# 06-MAC.net
KiCad netlist of a schematic drawn in Altium Designer
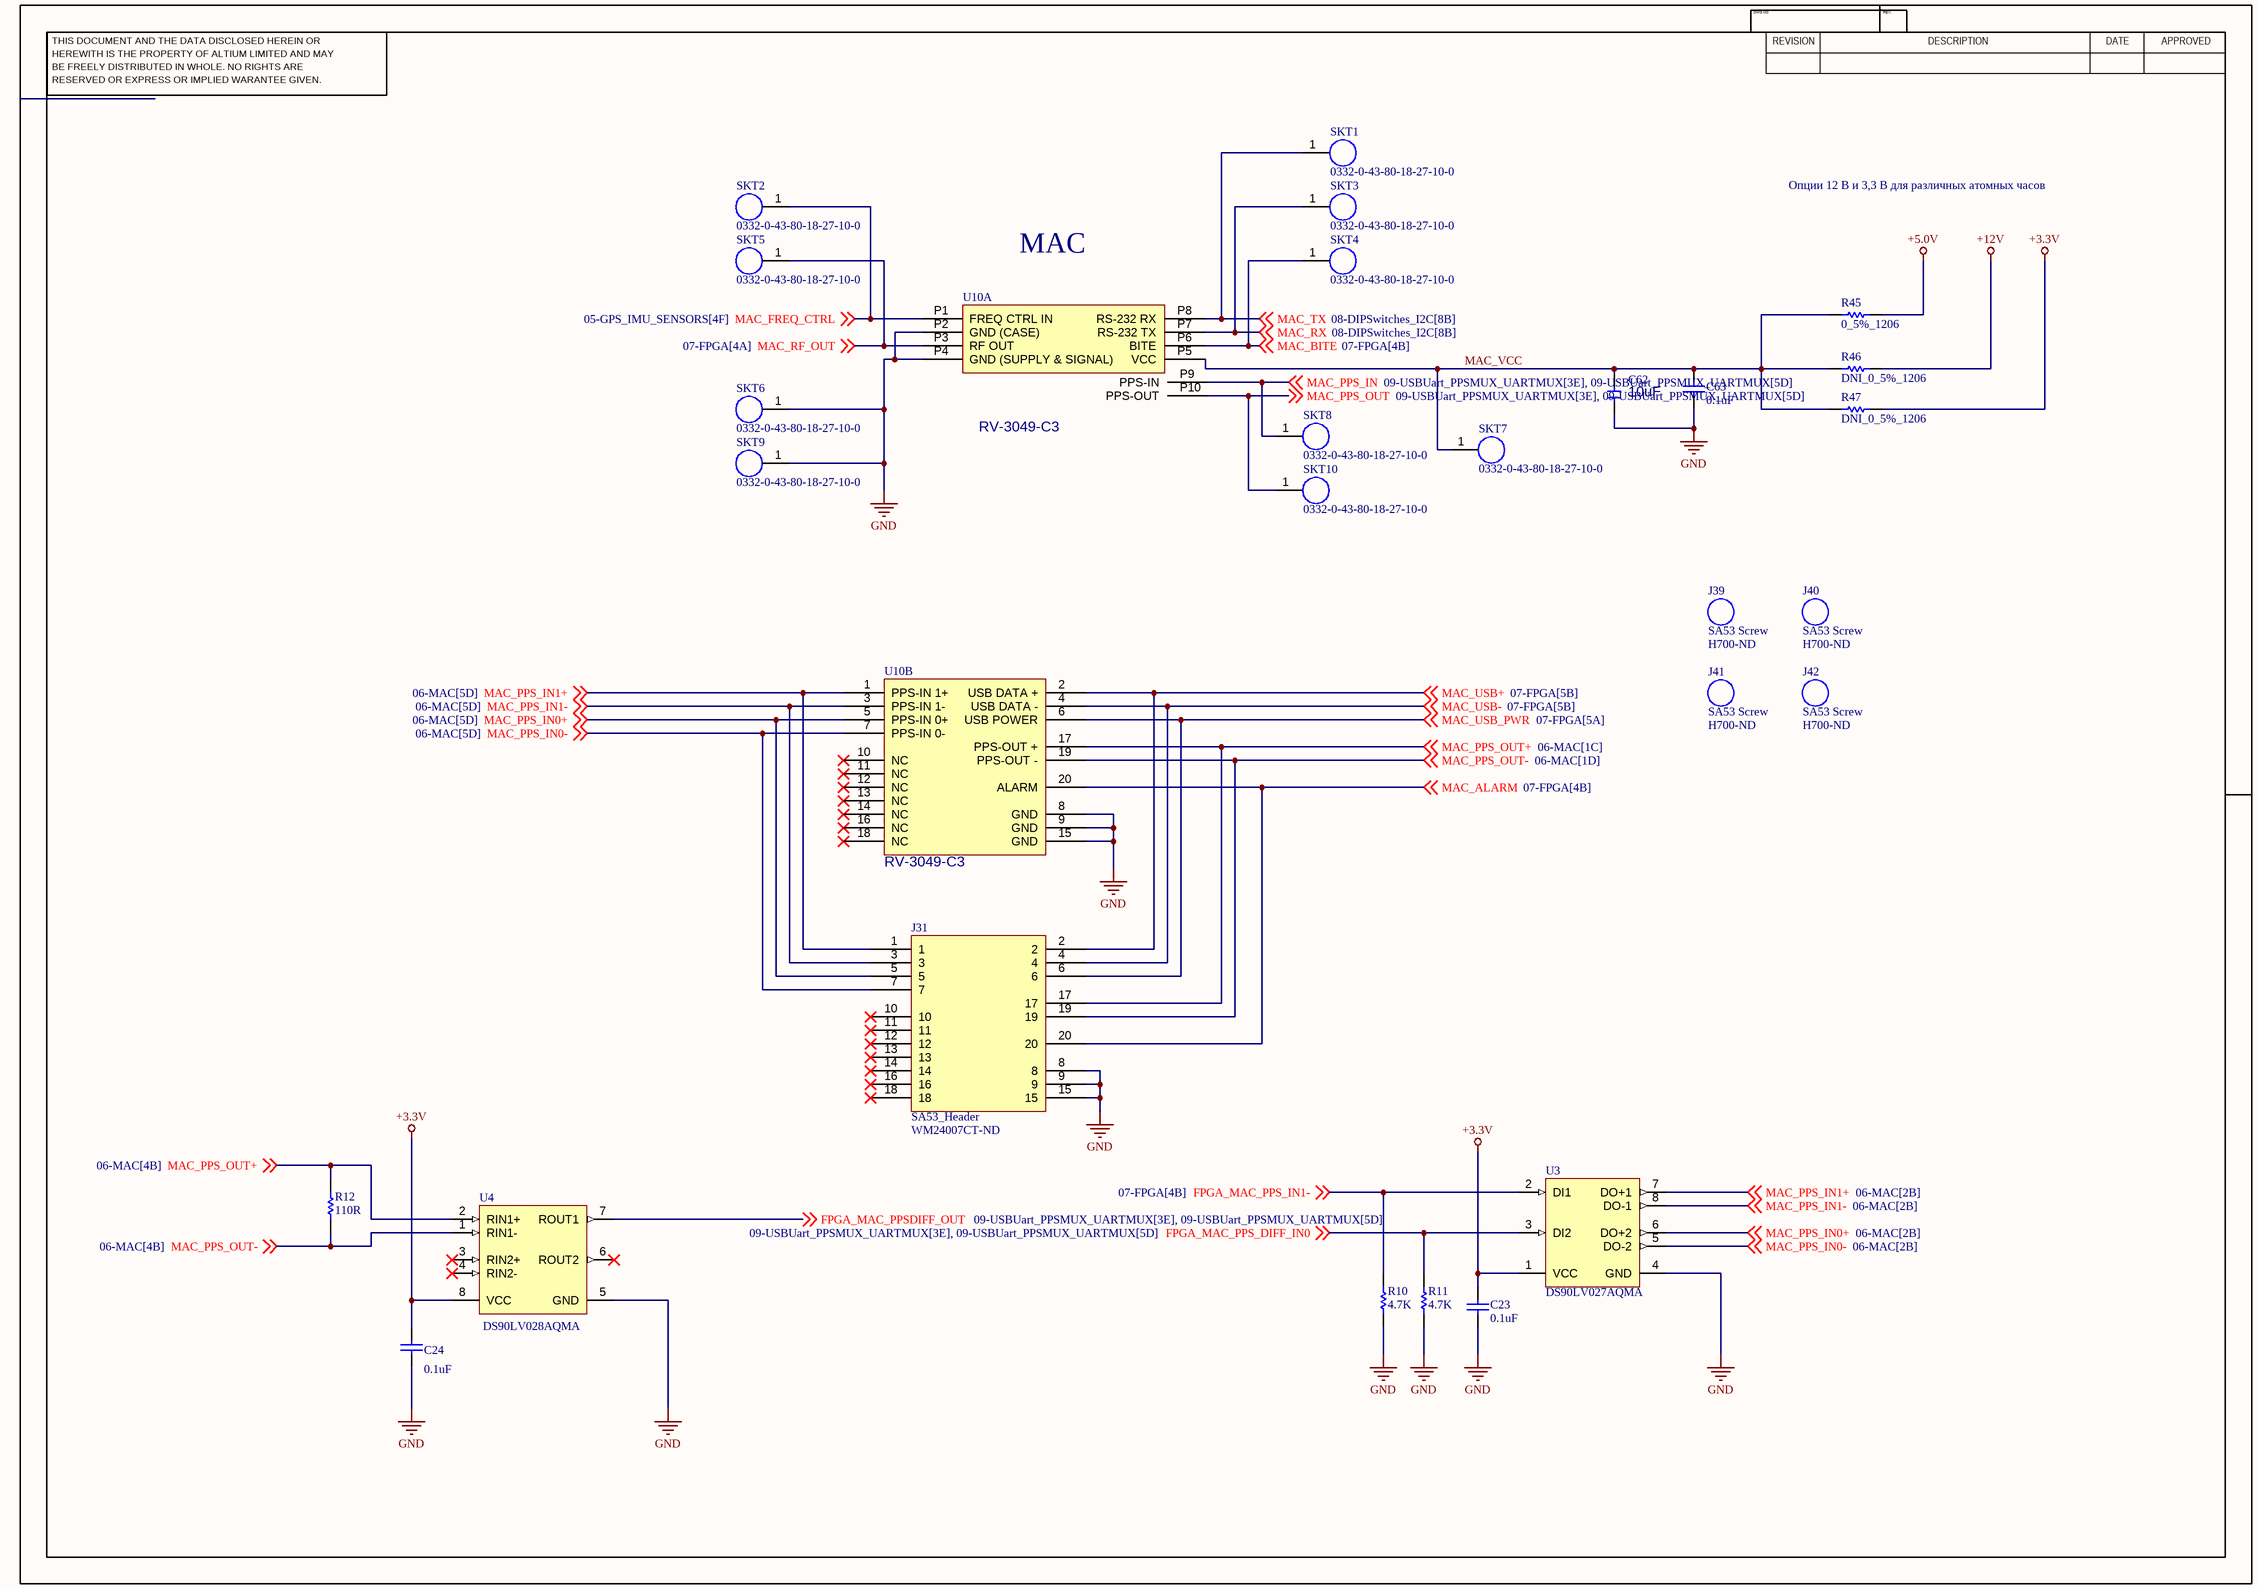
[diagram p0: 06-MAC.SchDoc]

(export (version "E")
  (design (tool "Eeschema 10.0.6"))
  (components
    (comp (ref "C23")
      (value "0.1uF")
      (footprint "CAPC1608X87X45ML20T05")
      (description "C0603X104K5RACAUTO")
      (fields (field (name "MANUFACTURER") "Kemet"))
      (libsource (lib "Altium Content Vault") (part "CAP"))
    )
    (comp (ref "C24")
      (value "0.1uF")
      (footprint "CAPC1608X87X45ML20T05")
      (description "C0603X104K5RACAUTO")
      (fields (field (name "MANUFACTURER") "Kemet"))
      (libsource (lib "Altium Content Vault") (part "CAP"))
    )
    (comp (ref "C62")
      (value "10uF")
      (footprint "CAPC2012X14N")
      (description "CAP, CER, 10.UF, 25V, 10%, X5R, 0805")
      (fields
        (field (name "MFG PART NUM") "TMK212BBJ106KG-T")
        (field (name "VALENTIUM PART NUM") "<VALENTIUM>")
      )
      (libsource (lib "Capacitors") (part "CAP_0805_10UF_25V"))
    )
    (comp (ref "C63")
      (value "0.1uF")
      (footprint "CAPC1608X87X45ML20T05")
      (description "C0603X104K5RACAUTO")
      (fields (field (name "MANUFACTURER") "Kemet"))
      (libsource (lib "Altium Content Vault") (part "CAP"))
    )
    (comp (ref "J31")
      (value "SA53_Header")
      (footprint "SA53_Header")
      (fields (field (name "SUPPLIER PART NUMBER 1") "WM24007CT-ND"))
      (libsource (lib "FPGA_CONN") (part "SA53_Header"))
    )
    (comp (ref "J39")
      (value "SA53 Screw")
      (fields (field (name "SUPPLIER PART NUMBER 1") "H700-ND"))
      (libsource (lib "FPGA_CONN") (part "SA53 Screw"))
    )
    (comp (ref "J40")
      (value "SA53 Screw")
      (fields (field (name "SUPPLIER PART NUMBER 1") "H700-ND"))
      (libsource (lib "FPGA_CONN") (part "SA53 Screw"))
    )
    (comp (ref "J41")
      (value "SA53 Screw")
      (fields (field (name "SUPPLIER PART NUMBER 1") "H700-ND"))
      (libsource (lib "FPGA_CONN") (part "SA53 Screw"))
    )
    (comp (ref "J42")
      (value "SA53 Screw")
      (fields (field (name "SUPPLIER PART NUMBER 1") "H700-ND"))
      (libsource (lib "FPGA_CONN") (part "SA53 Screw"))
    )
    (comp (ref "R10")
      (value "4.7K")
      (footprint "RESC1608X55X25LL10T15")
      (fields (field (name "MANUFACTURER") "Yageo") (field (name "TOLERANCE") "1%"))
      (libsource (lib "Altium Content Vault") (part "RES-2"))
    )
    (comp (ref "R11")
      (value "4.7K")
      (footprint "RESC1608X55X25LL10T15")
      (fields (field (name "MANUFACTURER") "Yageo") (field (name "TOLERANCE") "1%"))
      (libsource (lib "Altium Content Vault") (part "RES-2"))
    )
    (comp (ref "R12")
      (value "110R")
      (footprint "RESC1609X50X30NL10T20")
      (fields (field (name "PART NUMBER") "CRCW0603110RFKEA") (field (name "MANUFACTURER") "Vishay Dale"))
      (libsource (lib "Altium Content Vault") (part "RES"))
    )
    (comp (ref "R45")
      (value "0_5%_1206")
      (footprint "RESC3116X65X50ML20T20")
      (fields (field (name "PART NUMBER") "CRCW12060000Z0EAHP") (field (name "MANUFACTURER") "Vishay Dale"))
      (libsource (lib "Altium Content Vault") (part "RES"))
    )
    (comp (ref "R46")
      (value "DNI_0_5%_1206")
      (footprint "RESC3116X65X50ML20T20")
      (fields (field (name "PART NUMBER") "CRCW12060000Z0EAHP") (field (name "MANUFACTURER") "Vishay Dale"))
      (libsource (lib "Altium Content Vault") (part "RES"))
    )
    (comp (ref "R47")
      (value "DNI_0_5%_1206")
      (footprint "RESC3116X65X50ML20T20")
      (fields (field (name "PART NUMBER") "CRCW12060000Z0EAHP") (field (name "MANUFACTURER") "Vishay Dale"))
      (libsource (lib "Altium Content Vault") (part "RES"))
    )
    (comp (ref "SKT1")
      (value "0332-0-43-80-18-27-10-0")
      (footprint "SolderSocket")
      (description "Solder socket for pin headers")
      (libsource (lib "FPGA_CONN") (part "0332-0-43-80-18-27-10-0"))
    )
    (comp (ref "SKT2")
      (value "0332-0-43-80-18-27-10-0")
      (footprint "SolderSocket")
      (description "Solder socket for pin headers")
      (libsource (lib "FPGA_CONN") (part "0332-0-43-80-18-27-10-0"))
    )
    (comp (ref "SKT3")
      (value "0332-0-43-80-18-27-10-0")
      (footprint "SolderSocket")
      (description "Solder socket for pin headers")
      (libsource (lib "FPGA_CONN") (part "0332-0-43-80-18-27-10-0"))
    )
    (comp (ref "SKT4")
      (value "0332-0-43-80-18-27-10-0")
      (footprint "SolderSocket")
      (description "Solder socket for pin headers")
      (libsource (lib "FPGA_CONN") (part "0332-0-43-80-18-27-10-0"))
    )
    (comp (ref "SKT5")
      (value "0332-0-43-80-18-27-10-0")
      (footprint "SolderSocket")
      (description "Solder socket for pin headers")
      (libsource (lib "FPGA_CONN") (part "0332-0-43-80-18-27-10-0"))
    )
    (comp (ref "SKT6")
      (value "0332-0-43-80-18-27-10-0")
      (footprint "SolderSocket")
      (description "Solder socket for pin headers")
      (libsource (lib "FPGA_CONN") (part "0332-0-43-80-18-27-10-0"))
    )
    (comp (ref "SKT7")
      (value "0332-0-43-80-18-27-10-0")
      (footprint "SolderSocket")
      (description "Solder socket for pin headers")
      (libsource (lib "FPGA_CONN") (part "0332-0-43-80-18-27-10-0"))
    )
    (comp (ref "SKT8")
      (value "0332-0-43-80-18-27-10-0")
      (footprint "SolderSocket")
      (description "Solder socket for pin headers")
      (libsource (lib "FPGA_CONN") (part "0332-0-43-80-18-27-10-0"))
    )
    (comp (ref "SKT9")
      (value "0332-0-43-80-18-27-10-0")
      (footprint "SolderSocket")
      (description "Solder socket for pin headers")
      (libsource (lib "FPGA_CONN") (part "0332-0-43-80-18-27-10-0"))
    )
    (comp (ref "SKT10")
      (value "0332-0-43-80-18-27-10-0")
      (footprint "SolderSocket")
      (description "Solder socket for pin headers")
      (libsource (lib "FPGA_CONN") (part "0332-0-43-80-18-27-10-0"))
    )
    (comp (ref "U3")
      (value "DS90LV027AQMA")
      (footprint "M08A_N")
      (description "Automotive LVDS Dual Differential Driver, 8-pin Narrow SOIC")
      (fields (field (name "MANUFACTURER") "National Semiconductor"))
      (libsource (lib "Altium Content Vault") (part "IN-LNDRV-DS90LV027AHM"))
    )
    (comp (ref "U4")
      (value "DS90LV028AQMA")
      (footprint "M08A_L")
      (description "Automotive LVDS Dual Differential Line Receiver, 8-pin Narrow SOIC")
      (fields (field (name "MANUFACTURER") "National Semiconductor"))
      (libsource (lib "Altium Content Vault") (part "IN-LNRX-DS90LV028AHM"))
    )
    (comp (ref "U10")
      (value "RV-3049-C3")
      (footprint "SA53")
      (description "MOD, MAC, MAC-SA5X, ATOMIC CLOCK")
      (fields (field (name "MFG PART NUM") "MAC-SA5X") (field (name "VELENTIUM PART NUM") "<V PART NUM>"))
      (libsource (lib "") (part "MAC-SA5X_1"))
    )
  )
  (nets
    (net (code "1") (name "+3.3V") (class "Default")
      (node (ref "C23") (pin "2") (pinfunction "2_2") (pintype "passive"))
      (node (ref "C24") (pin "1") (pinfunction "1_1") (pintype "passive"))
      (node (ref "R47") (pin "2") (pinfunction "2_2") (pintype "passive"))
      (node (ref "U3") (pin "1") (pinfunction "VCC_1") (pintype "power_in"))
      (node (ref "U4") (pin "8") (pinfunction "VCC_8") (pintype "power_in"))
    )
    (net (code "2") (name "+5.0V") (class "Default")
      (node (ref "R45") (pin "2") (pinfunction "2_2") (pintype "passive"))
    )
    (net (code "3") (name "+12V") (class "Default")
      (node (ref "R46") (pin "2") (pinfunction "2_2") (pintype "passive"))
    )
    (net (code "4") (name "/MAC_VCC") (class "Default")
      (node (ref "C62") (pin "1") (pinfunction "1_1") (pintype "passive"))
      (node (ref "C63") (pin "2") (pinfunction "2_2") (pintype "passive"))
      (node (ref "R45") (pin "1") (pinfunction "1_1") (pintype "passive"))
      (node (ref "R46") (pin "1") (pinfunction "1_1") (pintype "passive"))
      (node (ref "R47") (pin "1") (pinfunction "1_1") (pintype "passive"))
      (node (ref "SKT7") (pin "1") (pinfunction "1_1") (pintype "passive"))
      (node (ref "U10") (pin "P5") (pinfunction "VCC_P5") (pintype "passive"))
    )
    (net (code "5") (name "FPGA_MAC_PPSDIFF_OUT") (class "Default")
      (node (ref "U4") (pin "7") (pinfunction "ROUT1_7") (pintype "output"))
    )
    (net (code "6") (name "FPGA_MAC_PPS_DIFF_IN0") (class "Default")
      (node (ref "R11") (pin "2") (pinfunction "2_2") (pintype "passive"))
      (node (ref "U3") (pin "3") (pinfunction "DI2_3") (pintype "input"))
    )
    (net (code "7") (name "FPGA_MAC_PPS_IN1-") (class "Default")
      (node (ref "R10") (pin "2") (pinfunction "2_2") (pintype "passive"))
      (node (ref "U3") (pin "2") (pinfunction "DI1_2") (pintype "input"))
    )
    (net (code "8") (name "GND") (class "Default")
      (node (ref "C23") (pin "1") (pinfunction "1_1") (pintype "passive"))
      (node (ref "C24") (pin "2") (pinfunction "2_2") (pintype "passive"))
      (node (ref "C62") (pin "2") (pinfunction "2_2") (pintype "passive"))
      (node (ref "C63") (pin "1") (pinfunction "1_1") (pintype "passive"))
      (node (ref "J31") (pin "15") (pinfunction "15_15") (pintype "passive"))
      (node (ref "J31") (pin "8") (pinfunction "8_8") (pintype "passive"))
      (node (ref "J31") (pin "9") (pinfunction "9_9") (pintype "passive"))
      (node (ref "R10") (pin "1") (pinfunction "1_1") (pintype "passive"))
      (node (ref "R11") (pin "1") (pinfunction "1_1") (pintype "passive"))
      (node (ref "SKT6") (pin "1") (pinfunction "1_1") (pintype "passive"))
      (node (ref "SKT9") (pin "1") (pinfunction "1_1") (pintype "passive"))
      (node (ref "U10") (pin "15") (pinfunction "GND_15") (pintype "passive"))
      (node (ref "U10") (pin "8") (pinfunction "GND_8") (pintype "passive"))
      (node (ref "U10") (pin "9") (pinfunction "GND_9") (pintype "passive"))
      (node (ref "U10") (pin "P2") (pinfunction "GND_(CASE)_P2") (pintype "passive"))
      (node (ref "U10") (pin "P4") (pinfunction "GND_(SUPPLY_&_SIGNAL)_P4") (pintype "passive"))
      (node (ref "U3") (pin "4") (pinfunction "GND_4") (pintype "power_in"))
      (node (ref "U4") (pin "5") (pinfunction "GND_5") (pintype "power_in"))
    )
    (net (code "9") (name "MAC_ALARM") (class "Default")
      (node (ref "J31") (pin "20") (pinfunction "20_20") (pintype "passive"))
      (node (ref "U10") (pin "20") (pinfunction "ALARM_20") (pintype "passive"))
    )
    (net (code "10") (name "MAC_BITE") (class "Default")
      (node (ref "SKT4") (pin "1") (pinfunction "1_1") (pintype "passive"))
      (node (ref "U10") (pin "P6") (pinfunction "BITE_P6") (pintype "passive"))
    )
    (net (code "11") (name "MAC_FREQ_CTRL") (class "Default")
      (node (ref "SKT2") (pin "1") (pinfunction "1_1") (pintype "passive"))
      (node (ref "U10") (pin "P1") (pinfunction "FREQ_CTRL_IN_P1") (pintype "passive"))
    )
    (net (code "12") (name "MAC_PPS_IN") (class "Default")
      (node (ref "SKT8") (pin "1") (pinfunction "1_1") (pintype "passive"))
      (node (ref "U10") (pin "P9") (pinfunction "PPS-IN_P9") (pintype "passive"))
    )
    (net (code "13") (name "MAC_PPS_IN0+") (class "Default")
      (node (ref "J31") (pin "5") (pinfunction "5_5") (pintype "passive"))
      (node (ref "U10") (pin "5") (pinfunction "PPS-IN_0+_5") (pintype "passive"))
      (node (ref "U3") (pin "6") (pinfunction "DO+2_6") (pintype "output"))
    )
    (net (code "14") (name "MAC_PPS_IN0-") (class "Default")
      (node (ref "J31") (pin "7") (pinfunction "7_7") (pintype "passive"))
      (node (ref "U10") (pin "7") (pinfunction "PPS-IN_0-_7") (pintype "passive"))
      (node (ref "U3") (pin "5") (pinfunction "DO-2_5") (pintype "output"))
    )
    (net (code "15") (name "MAC_PPS_IN1+") (class "Default")
      (node (ref "J31") (pin "1") (pinfunction "1_1") (pintype "passive"))
      (node (ref "U10") (pin "1") (pinfunction "PPS-IN_1+_1") (pintype "passive"))
      (node (ref "U3") (pin "7") (pinfunction "DO+1_7") (pintype "output"))
    )
    (net (code "16") (name "MAC_PPS_IN1-") (class "Default")
      (node (ref "J31") (pin "3") (pinfunction "3_3") (pintype "passive"))
      (node (ref "U10") (pin "3") (pinfunction "PPS-IN_1-_3") (pintype "passive"))
      (node (ref "U3") (pin "8") (pinfunction "DO-1_8") (pintype "output"))
    )
    (net (code "17") (name "MAC_PPS_OUT") (class "Default")
      (node (ref "SKT10") (pin "1") (pinfunction "1_1") (pintype "passive"))
      (node (ref "U10") (pin "P10") (pinfunction "PPS-OUT_P10") (pintype "passive"))
    )
    (net (code "18") (name "MAC_PPS_OUT+") (class "Default")
      (node (ref "J31") (pin "17") (pinfunction "17_17") (pintype "passive"))
      (node (ref "R12") (pin "2") (pinfunction "2_2") (pintype "passive"))
      (node (ref "U10") (pin "17") (pinfunction "PPS-OUT_+_17") (pintype "passive"))
      (node (ref "U4") (pin "2") (pinfunction "RIN1+_2") (pintype "input"))
    )
    (net (code "19") (name "MAC_PPS_OUT-") (class "Default")
      (node (ref "J31") (pin "19") (pinfunction "19_19") (pintype "passive"))
      (node (ref "R12") (pin "1") (pinfunction "1_1") (pintype "passive"))
      (node (ref "U10") (pin "19") (pinfunction "PPS-OUT_-_19") (pintype "passive"))
      (node (ref "U4") (pin "1") (pinfunction "RIN1-_1") (pintype "input"))
    )
    (net (code "20") (name "MAC_RF_OUT") (class "Default")
      (node (ref "SKT5") (pin "1") (pinfunction "1_1") (pintype "passive"))
      (node (ref "U10") (pin "P3") (pinfunction "RF_OUT_P3") (pintype "passive"))
    )
    (net (code "21") (name "MAC_RX") (class "Default")
      (node (ref "SKT3") (pin "1") (pinfunction "1_1") (pintype "passive"))
      (node (ref "U10") (pin "P7") (pinfunction "RS-232_TX_P7") (pintype "passive"))
    )
    (net (code "22") (name "MAC_TX") (class "Default")
      (node (ref "SKT1") (pin "1") (pinfunction "1_1") (pintype "passive"))
      (node (ref "U10") (pin "P8") (pinfunction "RS-232_RX_P8") (pintype "passive"))
    )
    (net (code "23") (name "MAC_USB+") (class "Default")
      (node (ref "J31") (pin "2") (pinfunction "2_2") (pintype "passive"))
      (node (ref "U10") (pin "2") (pinfunction "USB_DATA_+_2") (pintype "passive"))
    )
    (net (code "24") (name "MAC_USB-") (class "Default")
      (node (ref "J31") (pin "4") (pinfunction "4_4") (pintype "passive"))
      (node (ref "U10") (pin "4") (pinfunction "USB_DATA_-_4") (pintype "passive"))
    )
    (net (code "25") (name "MAC_USB_PWR") (class "Default")
      (node (ref "J31") (pin "6") (pinfunction "6_6") (pintype "passive"))
      (node (ref "U10") (pin "6") (pinfunction "USB_POWER_6") (pintype "passive"))
    )
    (net (code "26") (name "unconnected-(J31-Pad10)") (class "Default")
      (node (ref "J31") (pin "10") (pinfunction "10_10") (pintype "passive+no_connect"))
    )
    (net (code "27") (name "unconnected-(J31-Pad11)") (class "Default")
      (node (ref "J31") (pin "11") (pinfunction "11_11") (pintype "passive+no_connect"))
    )
    (net (code "28") (name "unconnected-(J31-Pad12)") (class "Default")
      (node (ref "J31") (pin "12") (pinfunction "12_12") (pintype "passive+no_connect"))
    )
    (net (code "29") (name "unconnected-(J31-Pad13)") (class "Default")
      (node (ref "J31") (pin "13") (pinfunction "13_13") (pintype "passive+no_connect"))
    )
    (net (code "30") (name "unconnected-(J31-Pad14)") (class "Default")
      (node (ref "J31") (pin "14") (pinfunction "14_14") (pintype "passive+no_connect"))
    )
    (net (code "31") (name "unconnected-(J31-Pad16)") (class "Default")
      (node (ref "J31") (pin "16") (pinfunction "16_16") (pintype "passive+no_connect"))
    )
    (net (code "32") (name "unconnected-(J31-Pad18)") (class "Default")
      (node (ref "J31") (pin "18") (pinfunction "18_18") (pintype "passive+no_connect"))
    )
    (net (code "33") (name "unconnected-(U4-RIN2+-Pad3)") (class "Default")
      (node (ref "U4") (pin "3") (pinfunction "RIN2+_3") (pintype "input+no_connect"))
    )
    (net (code "34") (name "unconnected-(U4-RIN2--Pad4)") (class "Default")
      (node (ref "U4") (pin "4") (pinfunction "RIN2-_4") (pintype "input+no_connect"))
    )
    (net (code "35") (name "unconnected-(U4-ROUT2-Pad6)") (class "Default")
      (node (ref "U4") (pin "6") (pinfunction "ROUT2_6") (pintype "output+no_connect"))
    )
    (net (code "36") (name "unconnected-(U10B-NC-Pad10)") (class "Default")
      (node (ref "U10") (pin "10") (pinfunction "NC_10") (pintype "passive+no_connect"))
    )
    (net (code "37") (name "unconnected-(U10B-NC-Pad11)") (class "Default")
      (node (ref "U10") (pin "11") (pinfunction "NC_11") (pintype "passive+no_connect"))
    )
    (net (code "38") (name "unconnected-(U10B-NC-Pad12)") (class "Default")
      (node (ref "U10") (pin "12") (pinfunction "NC_12") (pintype "passive+no_connect"))
    )
    (net (code "39") (name "unconnected-(U10B-NC-Pad13)") (class "Default")
      (node (ref "U10") (pin "13") (pinfunction "NC_13") (pintype "passive+no_connect"))
    )
    (net (code "40") (name "unconnected-(U10B-NC-Pad14)") (class "Default")
      (node (ref "U10") (pin "14") (pinfunction "NC_14") (pintype "passive+no_connect"))
    )
    (net (code "41") (name "unconnected-(U10B-NC-Pad16)") (class "Default")
      (node (ref "U10") (pin "16") (pinfunction "NC_16") (pintype "passive+no_connect"))
    )
    (net (code "42") (name "unconnected-(U10B-NC-Pad18)") (class "Default")
      (node (ref "U10") (pin "18") (pinfunction "NC_18") (pintype "passive+no_connect"))
    )
  )
)
